# test_led.net
KiCad netlist of a schematic drawn in Altium Designer
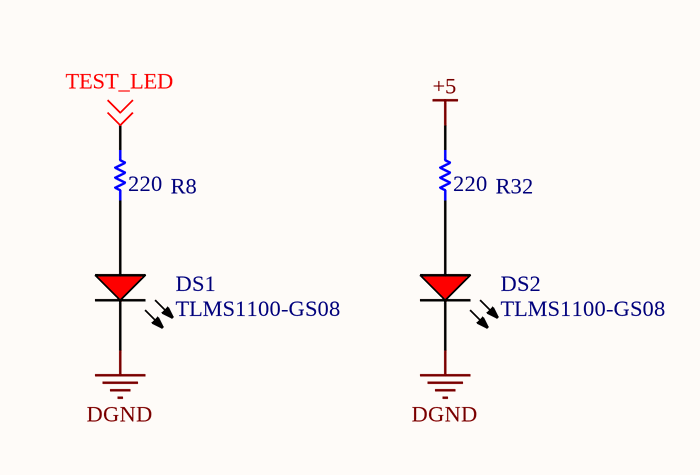
[diagram p0: test_led.SchDoc]

(export (version "E")
  (design (tool "Eeschema 10.0.6"))
  (components
    (comp (ref "DS1")
      (value "TLMS1100-GS08")
      (footprint "VISH-TLMX1100_V")
      (description "Red Led, 20mA, 2.1 V, -40 to 100 degC, 2-Pin SMD (0603), RoHS, Tape and Reel")
      (fields (field (name "MANUFACTURER") "Vishay Semiconductor") (field (name "POWER") "90mW"))
      (libsource (lib "Americas- CUAir- Cornell University") (part "LED-RED-AK-2"))
    )
    (comp (ref "DS2")
      (value "TLMS1100-GS08")
      (footprint "VISH-TLMX1100_V")
      (description "Red Led, 20mA, 2.1 V, -40 to 100 degC, 2-Pin SMD (0603), RoHS, Tape and Reel")
      (fields (field (name "MANUFACTURER") "Vishay Semiconductor") (field (name "POWER") "90mW"))
      (libsource (lib "Americas- CUAir- Cornell University") (part "LED-RED-AK-2"))
    )
    (comp (ref "R8")
      (value "220")
      (footprint "0805")
      (description "RES Thick Film, 220Ω, 0.125W, 150V, 0805")
      (fields (field (name "MPN") "0805W8F2200T5E") (field (name "JLCPCB PART #") "C17557"))
      (libsource (lib "JLCPCB Resistor Schematic Lib") (part "220"))
    )
    (comp (ref "R32")
      (value "220")
      (footprint "0805")
      (description "RES Thick Film, 220Ω, 0.125W, 150V, 0805")
      (fields (field (name "MPN") "0805W8F2200T5E") (field (name "JLCPCB PART #") "C17557"))
      (libsource (lib "JLCPCB Resistor Schematic Lib") (part "220"))
    )
  )
  (nets
    (net (code "1") (name "+5") (class "Default")
      (node (ref "R32") (pin "2") (pinfunction "2_2") (pintype "passive"))
    )
    (net (code "2") (name "DGND") (class "Default")
      (node (ref "DS1") (pin "2") (pinfunction "K_2") (pintype "passive"))
      (node (ref "DS2") (pin "2") (pinfunction "K_2") (pintype "passive"))
    )
    (net (code "3") (name "Net-(DS1-A)") (class "Default")
      (node (ref "DS1") (pin "1") (pinfunction "A_1") (pintype "passive"))
      (node (ref "R8") (pin "1") (pinfunction "1_1") (pintype "passive"))
    )
    (net (code "4") (name "Net-(DS2-A)") (class "Default")
      (node (ref "DS2") (pin "1") (pinfunction "A_1") (pintype "passive"))
      (node (ref "R32") (pin "1") (pinfunction "1_1") (pintype "passive"))
    )
    (net (code "5") (name "TEST_LED") (class "Default")
      (node (ref "R8") (pin "2") (pinfunction "2_2") (pintype "passive"))
    )
  )
)
